# 02A-001.net
KiCad netlist of a schematic drawn in EAGLE
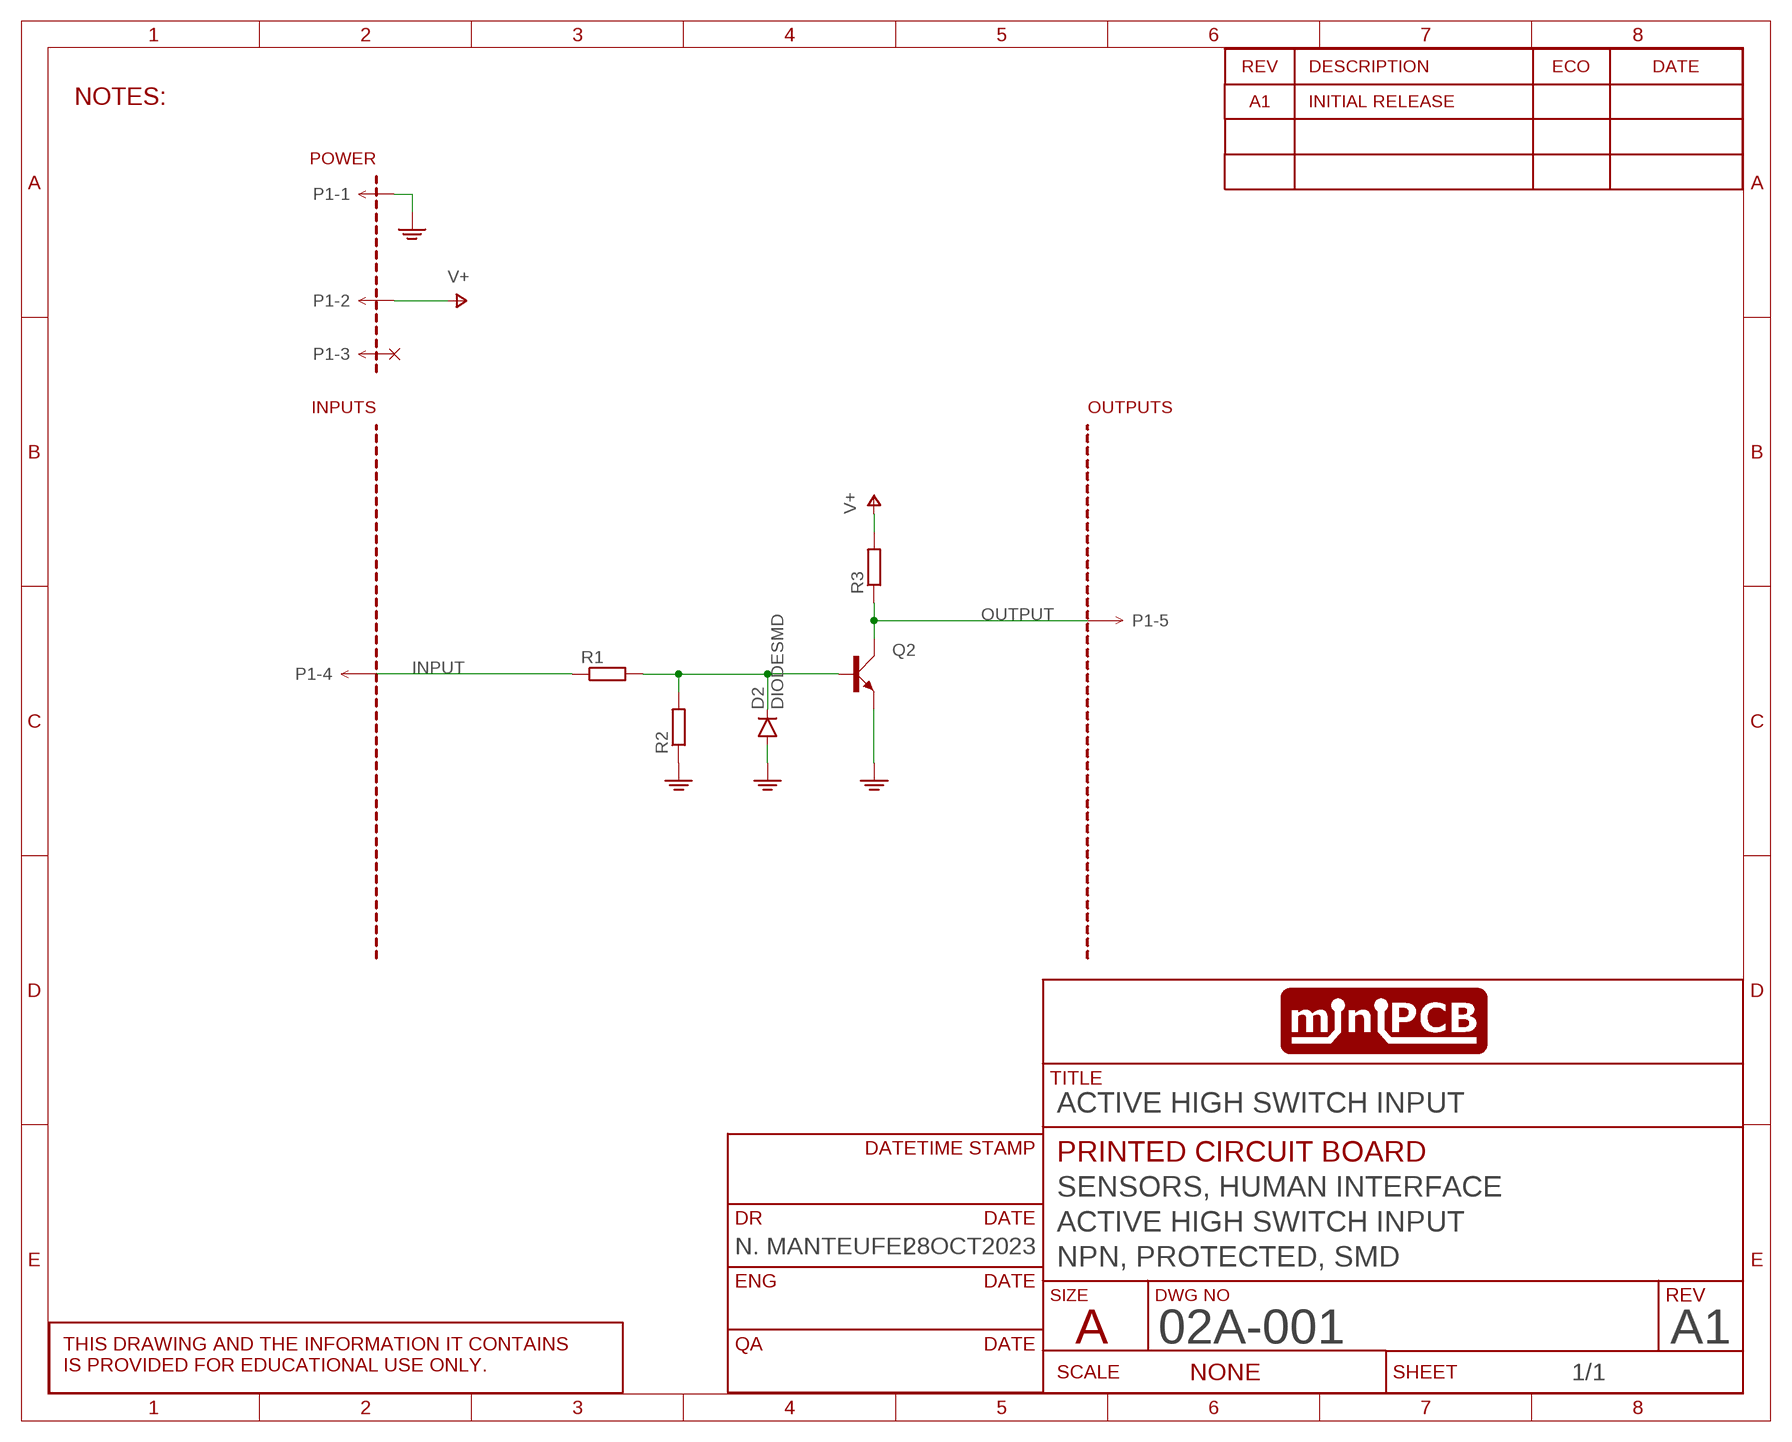
[diagram p0: schematic, sheet 1]

(export (version "E")
  (design (tool "Eeschema 10.0.6"))
  (components
    (comp (ref "D2")
      (value "DIODESMD")
      (footprint "eagle-import:DO214AC")
      (libsource (lib "eagle-import") (part "DIODESMD"))
    )
    (comp (ref "P1")
      (value "MINIPCB_5P5P")
      (footprint "eagle-import:PINS_1X5")
      (libsource (lib "eagle-import") (part "MINIPCB_5P5P"))
    )
    (comp (ref "PCB1")
      (value "MINIPCB_0P00A-20X25")
      (footprint "eagle-import:MINIPCB_00A_20X25")
      (fields (field (name "PART_NUMBER") "02A-001") (field (name "REVISION") "A1-01"))
      (libsource (lib "eagle-import") (part "MINIPCB_0P00A-20X25"))
    )
    (comp (ref "Q2")
      (value "BJT_NPNBEC")
      (footprint "eagle-import:SOT23")
      (libsource (lib "eagle-import") (part "BJT_NPNBEC"))
    )
    (comp (ref "R1")
      (value "RESISTORSMD")
      (footprint "eagle-import:R0805")
      (libsource (lib "eagle-import") (part "RESISTORSMD"))
    )
    (comp (ref "R2")
      (value "RESISTORSMD")
      (footprint "eagle-import:R0805")
      (libsource (lib "eagle-import") (part "RESISTORSMD"))
    )
    (comp (ref "R3")
      (value "RESISTORSMD")
      (footprint "eagle-import:R0805")
      (libsource (lib "eagle-import") (part "RESISTORSMD"))
    )
  )
  (nets
    (net (code "1") (name "/INPUT") (class "Default")
      (node (ref "P1") (pin "4") (pinfunction "1_4") (pintype "bidirectional"))
      (node (ref "R1") (pin "1") (pinfunction "1_1") (pintype "passive"))
    )
    (net (code "2") (name "/OUTPUT") (class "Default")
      (node (ref "P1") (pin "5") (pinfunction "1_5") (pintype "bidirectional"))
      (node (ref "Q2") (pin "3") (pinfunction "C_3") (pintype "passive"))
      (node (ref "R3") (pin "1") (pinfunction "1_1") (pintype "passive"))
    )
    (net (code "3") (name "GND") (class "Default")
      (node (ref "D2") (pin "A") (pinfunction "A_A") (pintype "passive"))
      (node (ref "P1") (pin "1") (pinfunction "1_1") (pintype "bidirectional"))
      (node (ref "Q2") (pin "2") (pinfunction "E_2") (pintype "passive"))
      (node (ref "R2") (pin "1") (pinfunction "1_1") (pintype "passive"))
    )
    (net (code "4") (name "Net-(Q2-B)") (class "Default")
      (node (ref "D2") (pin "C") (pinfunction "C_C") (pintype "passive"))
      (node (ref "Q2") (pin "1") (pinfunction "B_1") (pintype "passive"))
      (node (ref "R1") (pin "2") (pinfunction "2_2") (pintype "passive"))
      (node (ref "R2") (pin "2") (pinfunction "2_2") (pintype "passive"))
    )
    (net (code "5") (name "V+") (class "Default")
      (node (ref "P1") (pin "2") (pinfunction "1_2") (pintype "bidirectional"))
      (node (ref "R3") (pin "2") (pinfunction "2_2") (pintype "passive"))
    )
    (net (code "6") (name "unconnected-(P1C-1-Pad3)") (class "Default")
      (node (ref "P1") (pin "3") (pinfunction "1_3") (pintype "bidirectional"))
    )
  )
)
